# 02_MCU.net
KiCad netlist of a schematic drawn in Altium Designer
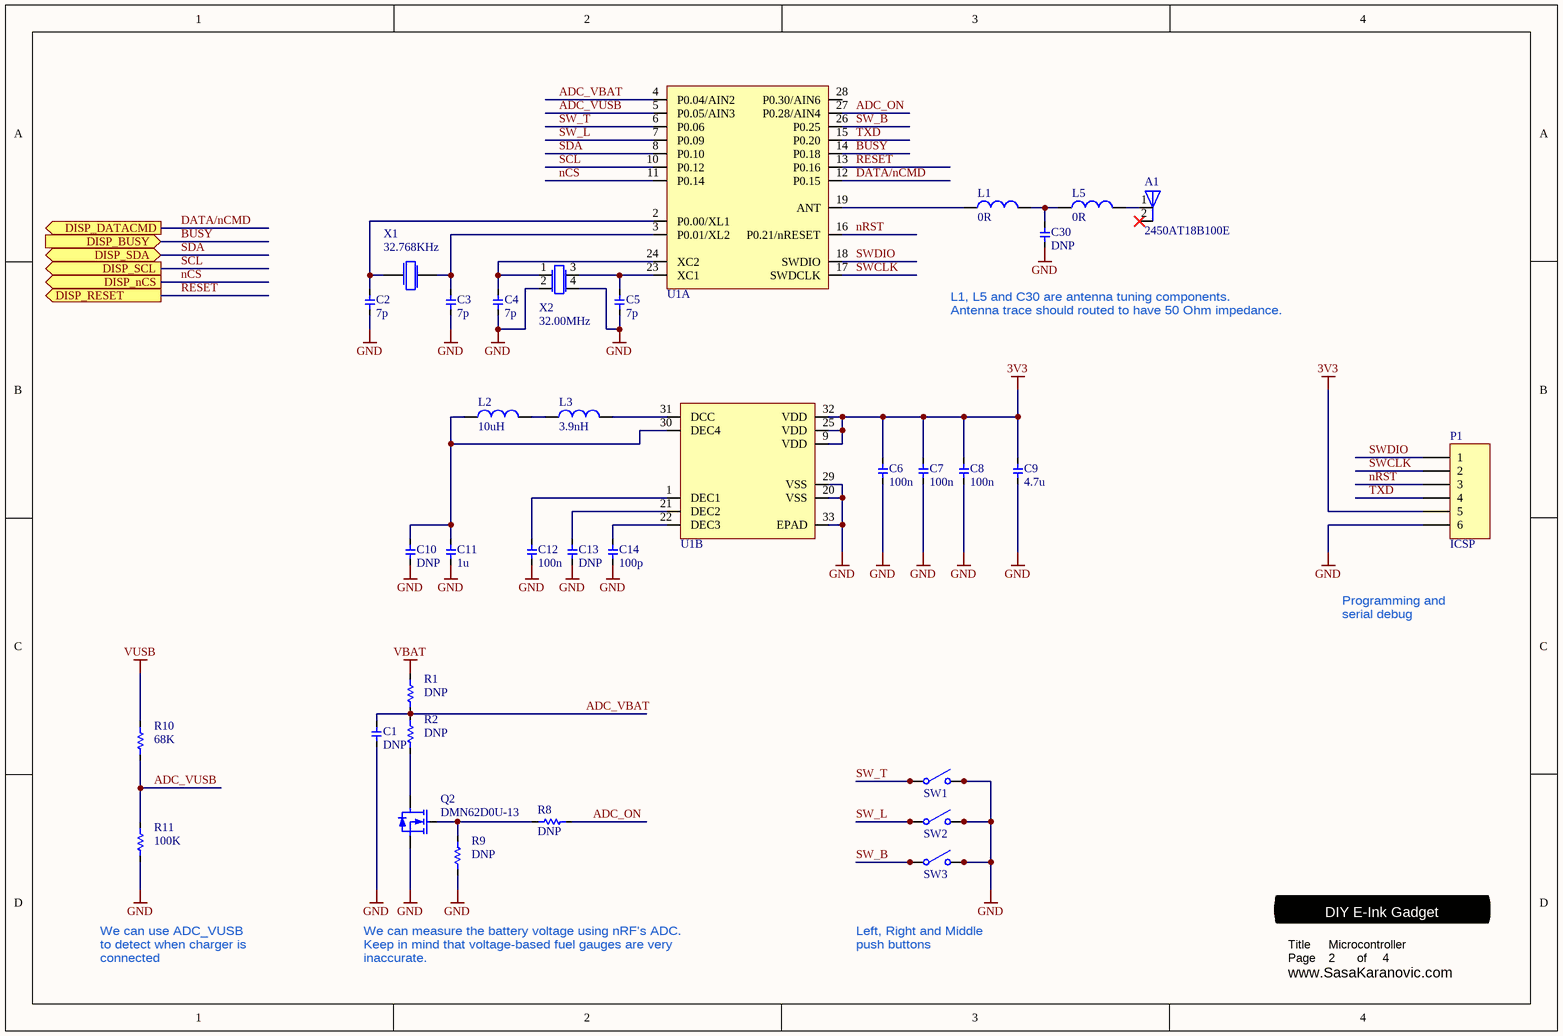
[diagram p0: 02_MCU.SchDoc]

(export (version "E")
  (design (tool "Eeschema 10.0.6"))
  (components
    (comp (ref "A1")
      (value "2450AT18B100E")
      (footprint "Footprint_Misc:2450AT18B100")
      (description "2.4GHz - Chip RF Antenna 2.4GHz ~ 2.5GHz 0.5dBi Solder Surface Mount")
      (fields
        (field (name "MANUFACTURER") "Johanson Technology Inc.")
        (field (name "DISTRIBUTOR PART NUMBER") "712-1006-1-ND")
      )
      (libsource (lib "Schematic_Misc") (part "2450AT18B100E"))
    )
    (comp (ref "C1")
      (value "DNP")
      (footprint "Footprint_Misc:0603 - CAP")
      (description "Capacitor")
      (fields (field (name "Comment") "Cap"))
      (libsource (lib "Schematic_Misc") (part "Cap"))
    )
    (comp (ref "C2")
      (value "7p")
      (footprint "Footprint_Misc:0603 - CAP")
      (description "Capacitor")
      (fields
        (field (name "MANUFACTURER") "Samsung Electro-Mechanics")
        (field (name "MANUFACTURER PART NUMBER") "CL10C070DB8NNNC")
      )
      (libsource (lib "Schematic_Misc") (part "Cap"))
    )
    (comp (ref "C3")
      (value "7p")
      (footprint "Footprint_Misc:0603 - CAP")
      (description "Capacitor")
      (fields
        (field (name "MANUFACTURER") "Samsung Electro-Mechanics")
        (field (name "MANUFACTURER PART NUMBER") "CL10C070DB8NNNC")
      )
      (libsource (lib "Schematic_Misc") (part "Cap"))
    )
    (comp (ref "C4")
      (value "7p")
      (footprint "Footprint_Misc:0603 - CAP")
      (description "Capacitor")
      (fields
        (field (name "MANUFACTURER") "Samsung Electro-Mechanics")
        (field (name "MANUFACTURER PART NUMBER") "CL10C070DB8NNNC")
      )
      (libsource (lib "Schematic_Misc") (part "Cap"))
    )
    (comp (ref "C5")
      (value "7p")
      (footprint "Footprint_Misc:0603 - CAP")
      (description "Capacitor")
      (fields
        (field (name "MANUFACTURER") "Samsung Electro-Mechanics")
        (field (name "MANUFACTURER PART NUMBER") "CL10C070DB8NNNC")
      )
      (libsource (lib "Schematic_Misc") (part "Cap"))
    )
    (comp (ref "C6")
      (value "100n")
      (footprint "Footprint_Misc:0603 - CAP")
      (description "Capacitor")
      (fields
        (field (name "MANUFACTURER") "Samsung Electro-Mechanics")
        (field (name "MANUFACTURER PART NUMBER") "CL10B104KB8NNWC")
      )
      (libsource (lib "Schematic_Misc") (part "Cap"))
    )
    (comp (ref "C7")
      (value "100n")
      (footprint "Footprint_Misc:0603 - CAP")
      (description "Capacitor")
      (fields
        (field (name "MANUFACTURER") "Samsung Electro-Mechanics")
        (field (name "MANUFACTURER PART NUMBER") "CL10B104KB8NNWC")
      )
      (libsource (lib "Schematic_Misc") (part "Cap"))
    )
    (comp (ref "C8")
      (value "100n")
      (footprint "Footprint_Misc:0603 - CAP")
      (description "Capacitor")
      (fields
        (field (name "MANUFACTURER") "Samsung Electro-Mechanics")
        (field (name "MANUFACTURER PART NUMBER") "CL10B104KB8NNWC")
      )
      (libsource (lib "Schematic_Misc") (part "Cap"))
    )
    (comp (ref "C9")
      (value "4.7u")
      (footprint "Footprint_Misc:0603 - CAP")
      (description "Capacitor")
      (fields
        (field (name "MANUFACTURER") "Samsung Electro-Mechanics")
        (field (name "MANUFACTURER PART NUMBER") "CL10B475KQ8NQNC")
      )
      (libsource (lib "Schematic_Misc") (part "Cap"))
    )
    (comp (ref "C10")
      (value "DNP")
      (footprint "Footprint_Misc:0603 - CAP")
      (description "Capacitor")
      (fields (field (name "Comment") "Cap"))
      (libsource (lib "Schematic_Misc") (part "Cap"))
    )
    (comp (ref "C11")
      (value "1u")
      (footprint "Footprint_Misc:0603 - CAP")
      (description "Capacitor")
      (fields
        (field (name "MANUFACTURER") "Samsung Electro-Mechanics")
        (field (name "MANUFACTURER PART NUMBER") "CL10B105KA8VPNC")
      )
      (libsource (lib "Schematic_Misc") (part "Cap"))
    )
    (comp (ref "C12")
      (value "100n")
      (footprint "Footprint_Misc:0603 - CAP")
      (description "Capacitor")
      (fields
        (field (name "MANUFACTURER") "Samsung Electro-Mechanics")
        (field (name "MANUFACTURER PART NUMBER") "CL10B104KB8NNWC")
      )
      (libsource (lib "Schematic_Misc") (part "Cap"))
    )
    (comp (ref "C13")
      (value "DNP")
      (footprint "Footprint_Misc:0603 - CAP")
      (description "Capacitor")
      (fields (field (name "Comment") "Cap"))
      (libsource (lib "Schematic_Misc") (part "Cap"))
    )
    (comp (ref "C14")
      (value "100p")
      (footprint "Footprint_Misc:0603 - CAP")
      (description "Capacitor")
      (fields
        (field (name "MANUFACTURER") "Samsung Electro-Mechanics")
        (field (name "MANUFACTURER PART NUMBER") "CL10C101JB8NNNC")
      )
      (libsource (lib "Schematic_Misc") (part "Cap"))
    )
    (comp (ref "C30")
      (value "DNP")
      (footprint "Footprint_Misc:0603 - CAP")
      (description "Capacitor")
      (fields (field (name "Comment") "Cap"))
      (libsource (lib "Schematic_Misc") (part "Cap"))
    )
    (comp (ref "L1")
      (value "0R")
      (footprint "Footprint_Misc:0603_IND")
      (description "Inductor")
      (fields
        (field (name "MANUFACTURER") "YAGEO")
        (field (name "MANUFACTURER PART NUMBER") "RC0603FR-070RL")
      )
      (libsource (lib "Schematic_Misc") (part "Inductor"))
    )
    (comp (ref "L2")
      (value "10uH")
      (footprint "Footprint_Misc:0603_IND")
      (description "Inductor")
      (fields
        (field (name "MANUFACTURER") "Abracon LLC")
        (field (name "MANUFACTURER PART NUMBER") "ASMCI-0603-100M-T")
      )
      (libsource (lib "Schematic_Misc") (part "Inductor"))
    )
    (comp (ref "L3")
      (value "3.9nH")
      (footprint "Footprint_Misc:0603_IND")
      (description "Inductor")
      (fields
        (field (name "MANUFACTURER") "Abracon LLC")
        (field (name "MANUFACTURER PART NUMBER") "AIMC-0603-3N9S-T")
      )
      (libsource (lib "Schematic_Misc") (part "Inductor"))
    )
    (comp (ref "L5")
      (value "0R")
      (footprint "Footprint_Misc:0603_IND")
      (description "Inductor")
      (fields
        (field (name "MANUFACTURER") "YAGEO")
        (field (name "MANUFACTURER PART NUMBER") "RC0603FR-070RL")
      )
      (libsource (lib "Schematic_Misc") (part "Inductor"))
    )
    (comp (ref "P1")
      (value "ICSP")
      (footprint "Footprint_Misc:Header 6x1 M - 90Deg - SMT")
      (description "Header, 6-Pin")
      (libsource (lib "Schematic_Misc") (part "Header 6"))
    )
    (comp (ref "Q2")
      (value "DMN62D0U-13")
      (footprint "Moji Footprintovi:SOT90P240X100-3N")
      (description "MOSFET N-CH 60V 0.38A")
      (fields
        (field (name "MANUFACTURER") "Diodes Incorporated")
        (field (name "DISTRIBUTOR PART NUMBER") "DMN62D0U-13DICT-ND")
      )
      (libsource (lib "Moji Schematici (1)") (part "DMN62D0U-13"))
    )
    (comp (ref "R1")
      (value "DNP")
      (footprint "Footprint_Misc:0603")
      (description "Resistor")
      (fields (field (name "Comment") "Res"))
      (libsource (lib "Schematic_Misc") (part "Res"))
    )
    (comp (ref "R2")
      (value "DNP")
      (footprint "Footprint_Misc:0603")
      (description "Resistor")
      (fields (field (name "Comment") "Res"))
      (libsource (lib "Schematic_Misc") (part "Res"))
    )
    (comp (ref "R8")
      (value "DNP")
      (footprint "Footprint_Misc:0603")
      (description "Resistor")
      (fields (field (name "Comment") "Res"))
      (libsource (lib "Schematic_Misc") (part "Res"))
    )
    (comp (ref "R9")
      (value "DNP")
      (footprint "Footprint_Misc:0603")
      (description "Resistor")
      (fields (field (name "Comment") "Res"))
      (libsource (lib "Schematic_Misc") (part "Res"))
    )
    (comp (ref "R10")
      (value "68K")
      (footprint "Footprint_Misc:0603")
      (description "Resistor")
      (fields
        (field (name "DISTRIBUTOR PART NUMBER") "311-68.0KHRCT-ND")
        (field (name "MANUFACTURER") "YAGEO")
      )
      (libsource (lib "Schematic_Misc") (part "Res"))
    )
    (comp (ref "R11")
      (value "100K")
      (footprint "Footprint_Misc:0603")
      (description "Resistor")
      (fields
        (field (name "DISTRIBUTOR PART NUMBER") "311-100KHRCT-ND")
        (field (name "MANUFACTURER") "YAGEO")
      )
      (libsource (lib "Schematic_Misc") (part "Res"))
    )
    (comp (ref "SW1")
      (value "SWITCH TACTILE SPST-NO 0.05A 12V")
      (footprint "Moji Footprintovi:PTS645")
      (fields
        (field (name "DISTRIBUTOR PART NUMBER") "CKN9088CT-ND")
        (field (name "MANUFACTURER") "C&K")
        (field (name "MANUFACTURER PART NUMBER") "PTS645SL50SMTR92 LFS")
      )
      (libsource (lib "Schematic_Misc") (part "PTS645SL50SMTR92 LFS"))
    )
    (comp (ref "SW2")
      (value "SWITCH TACTILE SPST-NO 0.05A 12V")
      (footprint "Moji Footprintovi:PTS645")
      (fields
        (field (name "DISTRIBUTOR PART NUMBER") "CKN9088CT-ND")
        (field (name "MANUFACTURER") "C&K")
        (field (name "MANUFACTURER PART NUMBER") "PTS645SL50SMTR92 LFS")
      )
      (libsource (lib "Schematic_Misc") (part "PTS645SL50SMTR92 LFS"))
    )
    (comp (ref "SW3")
      (value "SWITCH TACTILE SPST-NO 0.05A 12V")
      (footprint "Moji Footprintovi:PTS645")
      (fields
        (field (name "DISTRIBUTOR PART NUMBER") "CKN9088CT-ND")
        (field (name "MANUFACTURER") "C&K")
        (field (name "MANUFACTURER PART NUMBER") "PTS645SL50SMTR92 LFS")
      )
      (libsource (lib "Schematic_Misc") (part "PTS645SL50SMTR92 LFS"))
    )
    (comp (ref "U1")
      (value "NRF52810-QCAA-R")
      (footprint "Footprint_Misc:QFN50P500X500X100_HS-33N")
      (description "IC RF TxRx + MCU Bluetooth Bluetooth v5.0 2.4GHz 32-VFQFN Exposed Pad")
      (fields
        (field (name "MANUFACTURER") "Nordic Semiconductor ASA")
        (field (name "DISTRIBUTOR PART NUMBER") "1490-NRF52810-QCAA-RCT-ND")
      )
      (libsource (lib "Schematic_Misc") (part "NRF52810-QCAA-R"))
    )
    (comp (ref "X1")
      (value "32.768KHz")
      (footprint "Footprint_Misc:XTAL-2LEAD-3215")
      (description "32.768 kHz ±20ppm Crystal 7pF 70 kOhms 2-SMD, No Lead")
      (fields
        (field (name "MANUFACTURER") "ECS Inc.")
        (field (name "MANUFACTURER PART NUMBER") "ECS-320-8-37B-CKY-TR")
      )
      (libsource (lib "Schematic_Misc") (part "XTAL-32.768KHz-SC32S-7PF20PPM"))
    )
    (comp (ref "X2")
      (value "32.00MHz")
      (footprint "Footprint_Misc:XTAL-4LEAD-2016")
      (description "32 MHz ±10ppm Crystal 8pF 50 Ohms 4-SMD, No Lead")
      (fields
        (field (name "MANUFACTURER") "ECS Inc.")
        (field (name "MANUFACTURER PART NUMBER") "ECS-320-8-37B-CKY-TR")
      )
      (libsource (lib "Schematic_Misc") (part "XTAL-32MHz-ECS-320-8-37B-CKY-TR"))
    )
  )
  (nets
    (net (code "1") (name "/ADC_ON") (class "Default")
      (node (ref "R8") (pin "1") (pinfunction "1_1") (pintype "passive"))
      (node (ref "U1") (pin "27") (pinfunction "_P0.28/AIN4_27") (pintype "passive"))
    )
    (net (code "2") (name "/ADC_VBAT") (class "Default")
      (node (ref "C1") (pin "2") (pinfunction "2_2") (pintype "passive"))
      (node (ref "R1") (pin "1") (pinfunction "1_1") (pintype "passive"))
      (node (ref "R2") (pin "2") (pinfunction "2_2") (pintype "passive"))
      (node (ref "U1") (pin "4") (pinfunction "_P0.04/AIN2_4") (pintype "passive"))
    )
    (net (code "3") (name "/ADC_VUSB") (class "Default")
      (node (ref "R10") (pin "1") (pinfunction "1_1") (pintype "passive"))
      (node (ref "R11") (pin "2") (pinfunction "2_2") (pintype "passive"))
      (node (ref "U1") (pin "5") (pinfunction "_P0.05/AIN3_5") (pintype "passive"))
    )
    (net (code "4") (name "/BUSY") (class "Default")
      (node (ref "U1") (pin "14") (pinfunction "_P0.18_14") (pintype "passive"))
    )
    (net (code "5") (name "/DATA{slash}nCMD") (class "Default")
      (node (ref "U1") (pin "12") (pinfunction "_P0.15_12") (pintype "passive"))
    )
    (net (code "6") (name "/RESET") (class "Default")
      (node (ref "U1") (pin "13") (pinfunction "_P0.16_13") (pintype "passive"))
    )
    (net (code "7") (name "/SCL") (class "Default")
      (node (ref "U1") (pin "10") (pinfunction "_P0.12_10") (pintype "passive"))
    )
    (net (code "8") (name "/SDA") (class "Default")
      (node (ref "U1") (pin "8") (pinfunction "_P0.10_8") (pintype "passive"))
    )
    (net (code "9") (name "/SWCLK") (class "Default")
      (node (ref "P1") (pin "2") (pinfunction "2_2") (pintype "passive"))
      (node (ref "U1") (pin "17") (pinfunction "_SWDCLK_17") (pintype "passive"))
    )
    (net (code "10") (name "/SWDIO") (class "Default")
      (node (ref "P1") (pin "1") (pinfunction "1_1") (pintype "passive"))
      (node (ref "U1") (pin "18") (pinfunction "_SWDIO_18") (pintype "passive"))
    )
    (net (code "11") (name "/SW_B") (class "Default")
      (node (ref "SW3") (pin "1") (pinfunction "COMMON1_1") (pintype "passive"))
      (node (ref "SW3") (pin "2") (pinfunction "COMMON1_2") (pintype "passive"))
      (node (ref "U1") (pin "26") (pinfunction "_P0.25_26") (pintype "passive"))
    )
    (net (code "12") (name "/SW_L") (class "Default")
      (node (ref "SW2") (pin "1") (pinfunction "COMMON1_1") (pintype "passive"))
      (node (ref "SW2") (pin "2") (pinfunction "COMMON1_2") (pintype "passive"))
      (node (ref "U1") (pin "7") (pinfunction "_P0.09_7") (pintype "passive"))
    )
    (net (code "13") (name "/SW_T") (class "Default")
      (node (ref "SW1") (pin "1") (pinfunction "COMMON1_1") (pintype "passive"))
      (node (ref "SW1") (pin "2") (pinfunction "COMMON1_2") (pintype "passive"))
      (node (ref "U1") (pin "6") (pinfunction "_P0.06_6") (pintype "passive"))
    )
    (net (code "14") (name "/TXD") (class "Default")
      (node (ref "P1") (pin "4") (pinfunction "4_4") (pintype "passive"))
      (node (ref "U1") (pin "15") (pinfunction "_P0.20_15") (pintype "passive"))
    )
    (net (code "15") (name "/nCS") (class "Default")
      (node (ref "U1") (pin "11") (pinfunction "_P0.14_11") (pintype "passive"))
    )
    (net (code "16") (name "/nRST") (class "Default")
      (node (ref "P1") (pin "3") (pinfunction "3_3") (pintype "passive"))
      (node (ref "U1") (pin "16") (pinfunction "_P0.21/nRESET_16") (pintype "passive"))
    )
    (net (code "17") (name "3V3") (class "Default")
      (node (ref "C6") (pin "2") (pinfunction "2_2") (pintype "passive"))
      (node (ref "C7") (pin "2") (pinfunction "2_2") (pintype "passive"))
      (node (ref "C8") (pin "2") (pinfunction "2_2") (pintype "passive"))
      (node (ref "C9") (pin "2") (pinfunction "2_2") (pintype "passive"))
      (node (ref "P1") (pin "5") (pinfunction "5_5") (pintype "passive"))
      (node (ref "U1") (pin "25") (pinfunction "_VDD_25") (pintype "passive"))
      (node (ref "U1") (pin "32") (pinfunction "_VDD_32") (pintype "passive"))
      (node (ref "U1") (pin "9") (pinfunction "_VDD_9") (pintype "passive"))
    )
    (net (code "18") (name "GND") (class "Default")
      (node (ref "C1") (pin "1") (pinfunction "1_1") (pintype "passive"))
      (node (ref "C10") (pin "1") (pinfunction "1_1") (pintype "passive"))
      (node (ref "C11") (pin "1") (pinfunction "1_1") (pintype "passive"))
      (node (ref "C12") (pin "1") (pinfunction "1_1") (pintype "passive"))
      (node (ref "C13") (pin "1") (pinfunction "1_1") (pintype "passive"))
      (node (ref "C14") (pin "1") (pinfunction "1_1") (pintype "passive"))
      (node (ref "C2") (pin "1") (pinfunction "1_1") (pintype "passive"))
      (node (ref "C3") (pin "1") (pinfunction "1_1") (pintype "passive"))
      (node (ref "C30") (pin "1") (pinfunction "1_1") (pintype "passive"))
      (node (ref "C4") (pin "1") (pinfunction "1_1") (pintype "passive"))
      (node (ref "C5") (pin "1") (pinfunction "1_1") (pintype "passive"))
      (node (ref "C6") (pin "1") (pinfunction "1_1") (pintype "passive"))
      (node (ref "C7") (pin "1") (pinfunction "1_1") (pintype "passive"))
      (node (ref "C8") (pin "1") (pinfunction "1_1") (pintype "passive"))
      (node (ref "C9") (pin "1") (pinfunction "1_1") (pintype "passive"))
      (node (ref "P1") (pin "6") (pinfunction "6_6") (pintype "passive"))
      (node (ref "Q2") (pin "2") (pinfunction "S_2") (pintype "passive"))
      (node (ref "R11") (pin "1") (pinfunction "1_1") (pintype "passive"))
      (node (ref "R9") (pin "1") (pinfunction "1_1") (pintype "passive"))
      (node (ref "SW1") (pin "3") (pinfunction "COMMON2_3") (pintype "passive"))
      (node (ref "SW1") (pin "4") (pinfunction "COMMON2_4") (pintype "passive"))
      (node (ref "SW2") (pin "3") (pinfunction "COMMON2_3") (pintype "passive"))
      (node (ref "SW2") (pin "4") (pinfunction "COMMON2_4") (pintype "passive"))
      (node (ref "SW3") (pin "3") (pinfunction "COMMON2_3") (pintype "passive"))
      (node (ref "SW3") (pin "4") (pinfunction "COMMON2_4") (pintype "passive"))
      (node (ref "U1") (pin "20") (pinfunction "_VSS_20") (pintype "passive"))
      (node (ref "U1") (pin "29") (pinfunction "_VSS_29") (pintype "passive"))
      (node (ref "U1") (pin "33") (pinfunction "EPAD_33") (pintype "passive"))
      (node (ref "X2") (pin "2") (pinfunction "GND_2") (pintype "passive"))
      (node (ref "X2") (pin "4") (pinfunction "GND_4") (pintype "passive"))
    )
    (net (code "19") (name "Net-(A1-FEED)") (class "Default")
      (node (ref "A1") (pin "1") (pinfunction "FEED_1") (pintype "passive"))
      (node (ref "L5") (pin "2") (pinfunction "2_2") (pintype "passive"))
    )
    (net (code "20") (name "Net-(C30-Pad2)") (class "Default")
      (node (ref "C30") (pin "2") (pinfunction "2_2") (pintype "passive"))
      (node (ref "L1") (pin "2") (pinfunction "2_2") (pintype "passive"))
      (node (ref "L5") (pin "1") (pinfunction "1_1") (pintype "passive"))
    )
    (net (code "21") (name "Net-(L2-Pad2)") (class "Default")
      (node (ref "L2") (pin "2") (pinfunction "2_2") (pintype "passive"))
      (node (ref "L3") (pin "1") (pinfunction "1_1") (pintype "passive"))
    )
    (net (code "22") (name "Net-(Q2-D)") (class "Default")
      (node (ref "Q2") (pin "3") (pinfunction "D_3") (pintype "passive"))
      (node (ref "R2") (pin "1") (pinfunction "1_1") (pintype "passive"))
    )
    (net (code "23") (name "Net-(Q2-G)") (class "Default")
      (node (ref "Q2") (pin "1") (pinfunction "G_1") (pintype "passive"))
      (node (ref "R8") (pin "2") (pinfunction "2_2") (pintype "passive"))
      (node (ref "R9") (pin "2") (pinfunction "2_2") (pintype "passive"))
    )
    (net (code "24") (name "Net-(U1A-_ANT)") (class "Default")
      (node (ref "L1") (pin "1") (pinfunction "1_1") (pintype "passive"))
      (node (ref "U1") (pin "19") (pinfunction "_ANT_19") (pintype "passive"))
    )
    (net (code "25") (name "Net-(U1A-_P0.00{slash}XL1)") (class "Default")
      (node (ref "C2") (pin "2") (pinfunction "2_2") (pintype "passive"))
      (node (ref "U1") (pin "2") (pinfunction "_P0.00/XL1_2") (pintype "passive"))
      (node (ref "X1") (pin "1") (pintype "passive"))
    )
    (net (code "26") (name "Net-(U1A-_P0.01{slash}XL2)") (class "Default")
      (node (ref "C3") (pin "2") (pinfunction "2_2") (pintype "passive"))
      (node (ref "U1") (pin "3") (pinfunction "_P0.01/XL2_3") (pintype "passive"))
      (node (ref "X1") (pin "2") (pintype "passive"))
    )
    (net (code "27") (name "Net-(U1A-_XC1)") (class "Default")
      (node (ref "C5") (pin "2") (pinfunction "2_2") (pintype "passive"))
      (node (ref "U1") (pin "23") (pinfunction "_XC1_23") (pintype "passive"))
      (node (ref "X2") (pin "3") (pinfunction "OSC3_3") (pintype "passive"))
    )
    (net (code "28") (name "Net-(U1A-_XC2)") (class "Default")
      (node (ref "C4") (pin "2") (pinfunction "2_2") (pintype "passive"))
      (node (ref "U1") (pin "24") (pinfunction "_XC2_24") (pintype "passive"))
      (node (ref "X2") (pin "1") (pinfunction "OSC1_1") (pintype "passive"))
    )
    (net (code "29") (name "Net-(U1B-_DCC)") (class "Default")
      (node (ref "L3") (pin "2") (pinfunction "2_2") (pintype "passive"))
      (node (ref "U1") (pin "31") (pinfunction "_DCC_31") (pintype "passive"))
    )
    (net (code "30") (name "Net-(U1B-_DEC1)") (class "Default")
      (node (ref "C12") (pin "2") (pinfunction "2_2") (pintype "passive"))
      (node (ref "U1") (pin "1") (pinfunction "_DEC1_1") (pintype "passive"))
    )
    (net (code "31") (name "Net-(U1B-_DEC2)") (class "Default")
      (node (ref "C13") (pin "2") (pinfunction "2_2") (pintype "passive"))
      (node (ref "U1") (pin "21") (pinfunction "_DEC2_21") (pintype "passive"))
    )
    (net (code "32") (name "Net-(U1B-_DEC3)") (class "Default")
      (node (ref "C14") (pin "2") (pinfunction "2_2") (pintype "passive"))
      (node (ref "U1") (pin "22") (pinfunction "_DEC3_22") (pintype "passive"))
    )
    (net (code "33") (name "Net-(U1B-_DEC4)") (class "Default")
      (node (ref "C10") (pin "2") (pinfunction "2_2") (pintype "passive"))
      (node (ref "C11") (pin "2") (pinfunction "2_2") (pintype "passive"))
      (node (ref "L2") (pin "1") (pinfunction "1_1") (pintype "passive"))
      (node (ref "U1") (pin "30") (pinfunction "_DEC4_30") (pintype "passive"))
    )
    (net (code "34") (name "VBAT") (class "Default")
      (node (ref "R1") (pin "2") (pinfunction "2_2") (pintype "passive"))
    )
    (net (code "35") (name "VUSB") (class "Default")
      (node (ref "R10") (pin "2") (pinfunction "2_2") (pintype "passive"))
    )
    (net (code "36") (name "unconnected-(A1-NC-Pad2)") (class "Default")
      (node (ref "A1") (pin "2") (pinfunction "NC_2") (pintype "passive+no_connect"))
    )
    (net (code "37") (name "unconnected-(U1A-_P0.30{slash}AIN6-Pad28)") (class "Default")
      (node (ref "U1") (pin "28") (pinfunction "_P0.30/AIN6_28") (pintype "passive"))
    )
  )
)
